# SH5_-_5V_VICOR_DCDC.net
KiCad netlist of a schematic drawn in Altium Designer
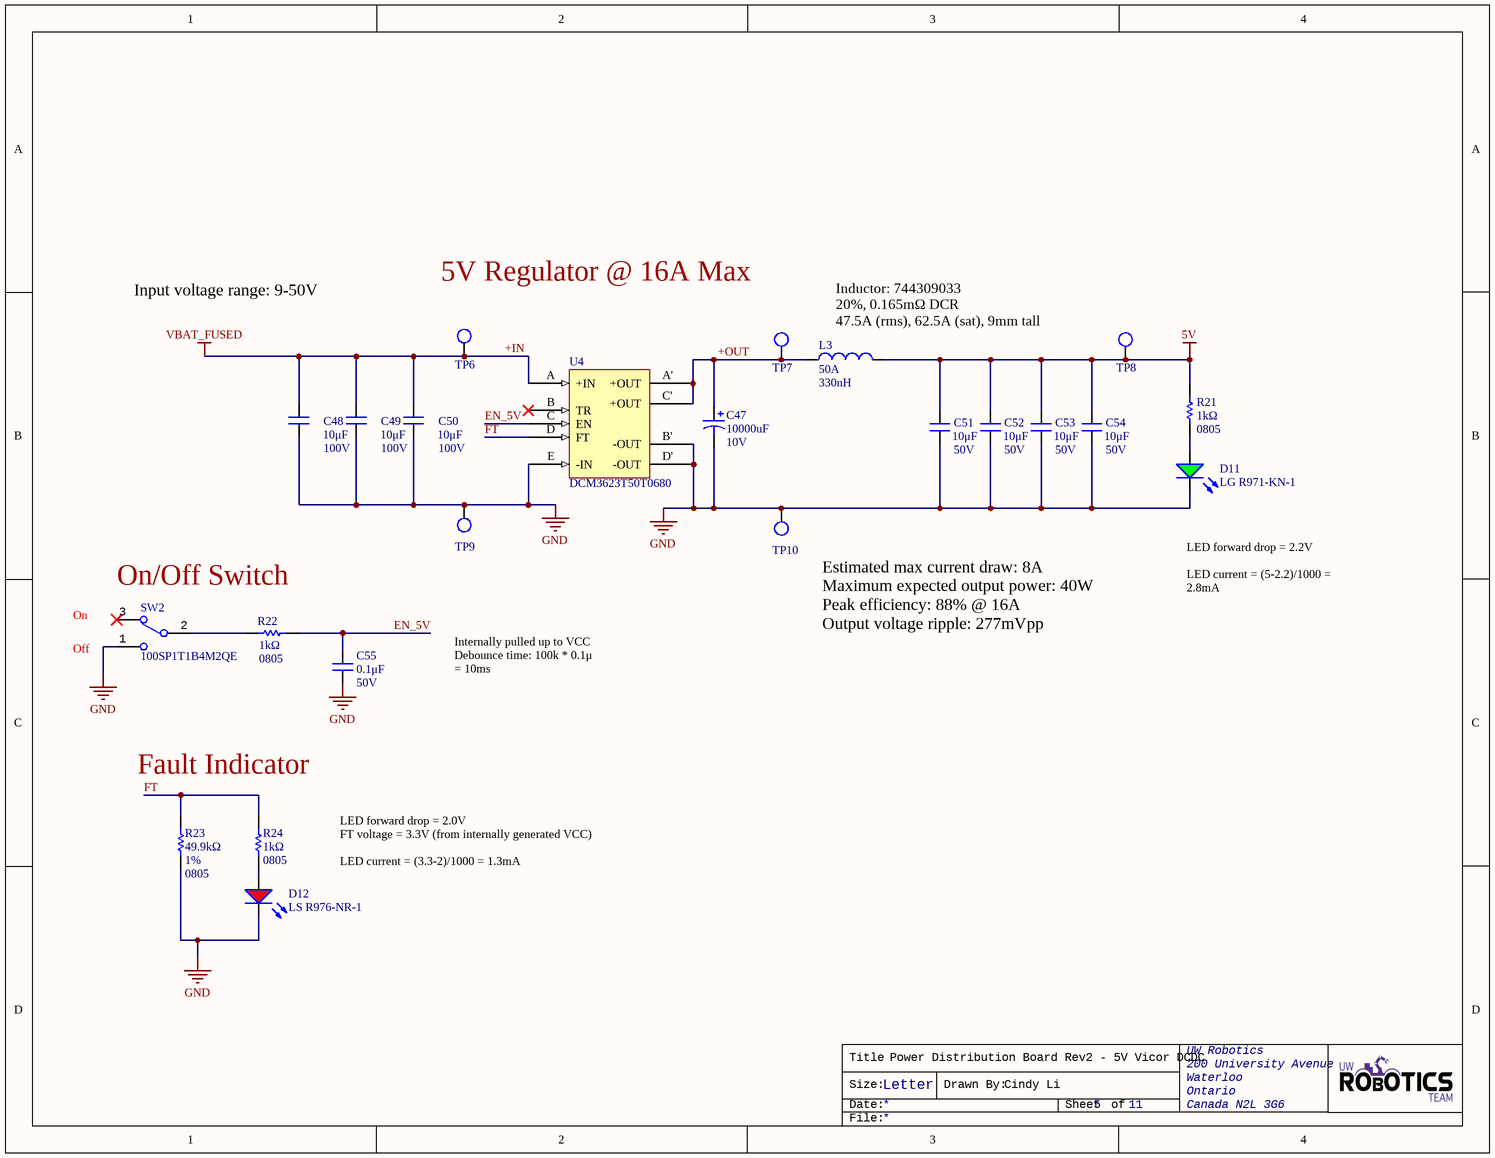
[diagram p0: SH5 - 5V VICOR DCDC.SchDoc]

(export (version "E")
  (design (tool "Eeschema 10.0.6"))
  (components
    (comp (ref "C47")
      (value "URS1A103MHD1TN")
      (footprint "CAP_UBY_18X25_NC")
      (description "CAP ALUM 10000UF 20% 10V RADIAL")
      (fields
        (field (name "TOLERANCE") "20%")
        (field (name "CAPACITANCE") "10000uF")
        (field (name "VOLTAGE RATING") "10V")
      )
      (libsource (lib "UWRT_Schematic_Library_2020") (part "URS1A103MHD1TN"))
    )
    (comp (ref "C48")
      (value "10μF")
      (footprint "CAP1210")
      (description "CAP CER 10uF 100V X7S 10% 1210")
      (fields
        (field (name "TOLERANCE") "10%")
        (field (name "VOLTAGE RATING") "100V")
        (field (name "Comment") "CAP_10uF_100V_1210")
      )
      (libsource (lib "UWRT_Schematic_Library_2020") (part "CAP_10uF_100V_1210"))
    )
    (comp (ref "C49")
      (value "10μF")
      (footprint "CAP1210")
      (description "CAP CER 10uF 100V X7S 10% 1210")
      (fields
        (field (name "TOLERANCE") "10%")
        (field (name "VOLTAGE RATING") "100V")
        (field (name "Comment") "CAP_10uF_100V_1210")
      )
      (libsource (lib "UWRT_Schematic_Library_2020") (part "CAP_10uF_100V_1210"))
    )
    (comp (ref "C50")
      (value "10μF")
      (footprint "CAP1210")
      (description "CAP CER 10uF 100V X7S 10% 1210")
      (fields
        (field (name "TOLERANCE") "10%")
        (field (name "VOLTAGE RATING") "100V")
        (field (name "Comment") "CAP_10uF_100V_1210")
      )
      (libsource (lib "UWRT_Schematic_Library_2020") (part "CAP_10uF_100V_1210"))
    )
    (comp (ref "C51")
      (value "10μF")
      (footprint "CAP1210")
      (description "CAP CER 10UF 50V X7R 1210")
      (fields
        (field (name "VOLTAGE RATING") "50V")
        (field (name "TOLERANCE") "20%")
        (field (name "Comment") "CAP_10uF_50V_1210")
      )
      (libsource (lib "UWRT_Schematic_Library_2020") (part "CAP_10uF_50V_1210"))
    )
    (comp (ref "C52")
      (value "10μF")
      (footprint "CAP1210")
      (description "CAP CER 10UF 50V X7R 1210")
      (fields
        (field (name "VOLTAGE RATING") "50V")
        (field (name "TOLERANCE") "20%")
        (field (name "Comment") "CAP_10uF_50V_1210")
      )
      (libsource (lib "UWRT_Schematic_Library_2020") (part "CAP_10uF_50V_1210"))
    )
    (comp (ref "C53")
      (value "10μF")
      (footprint "CAP1210")
      (description "CAP CER 10UF 50V X7R 1210")
      (fields
        (field (name "VOLTAGE RATING") "50V")
        (field (name "TOLERANCE") "20%")
        (field (name "Comment") "CAP_10uF_50V_1210")
      )
      (libsource (lib "UWRT_Schematic_Library_2020") (part "CAP_10uF_50V_1210"))
    )
    (comp (ref "C54")
      (value "10μF")
      (footprint "CAP1210")
      (description "CAP CER 10UF 50V X7R 1210")
      (fields
        (field (name "VOLTAGE RATING") "50V")
        (field (name "TOLERANCE") "20%")
        (field (name "Comment") "CAP_10uF_50V_1210")
      )
      (libsource (lib "UWRT_Schematic_Library_2020") (part "CAP_10uF_50V_1210"))
    )
    (comp (ref "C55")
      (value "0.1μF")
      (footprint "CAP2012")
      (description "CAP CER 0.1UF 50V X7R 0805")
      (fields (field (name "VOLTAGE RATING") "50V") (field (name "TOLERANCE") "10%"))
      (libsource (lib "UWRT_Schematic_Library_2020") (part "CAP_0.1uF_50V_0805"))
    )
    (comp (ref "D11")
      (value "LG R971-KN-1")
      (footprint "LED_0805_GREEN")
      (description "LED GREEN DIFFUSED 0805 SMD")
      (libsource (lib "UWRT_Schematic_Library_2020") (part "DIO_LED_G"))
    )
    (comp (ref "D12")
      (value "LS R976-NR-1")
      (footprint "LED_0805_RED")
      (description "LED RED DIFFUSED 0805 SMD")
      (libsource (lib "UWRT_Schematic_Library_2020") (part "DIO_LED_R"))
    )
    (comp (ref "L3")
      (value "744309033")
      (footprint "WE-HCM 1390")
      (description "IND 330NH 47.5A 0.165 MOHM")
      (fields
        (field (name "TOLERANCE") "20%")
        (field (name "MAX DC CURRENT") "50A")
        (field (name "INDUCTANCE") "330nH")
      )
      (libsource (lib "UWRT_Schematic_Library_2020") (part "744309033"))
    )
    (comp (ref "R21")
      (value "1kΩ")
      (footprint "RESC2012X60N")
      (description "RES 1K OHM 1% 1/8W 0805")
      (fields (field (name "TOLERANCE") "1%") (field (name "CASE CODE (IMPERIAL)") "0805"))
      (libsource (lib "UWRT_Schematic_Library_2020") (part "RES_1kΩ_0805_1%"))
    )
    (comp (ref "R22")
      (value "1kΩ")
      (footprint "RESC2012X60N")
      (description "RES 1K OHM 1% 1/8W 0805")
      (fields (field (name "TOLERANCE") "1%") (field (name "CASE CODE (IMPERIAL)") "0805"))
      (libsource (lib "UWRT_Schematic_Library_2020") (part "RES_1kΩ_0805_1%"))
    )
    (comp (ref "R23")
      (value "49.9kΩ")
      (footprint "RESC2012X60N")
      (description "RES 49.9K OHM 1% 1/8W 0805")
      (fields (field (name "TOLERANCE") "1%") (field (name "CASE CODE (IMPERIAL)") "0805"))
      (libsource (lib "UWRT_Schematic_Library_2020") (part "RES_49.9kΩ_0805_1%"))
    )
    (comp (ref "R24")
      (value "1kΩ")
      (footprint "RESC2012X60N")
      (description "RES 1K OHM 1% 1/8W 0805")
      (fields (field (name "TOLERANCE") "1%") (field (name "CASE CODE (IMPERIAL)") "0805"))
      (libsource (lib "UWRT_Schematic_Library_2020") (part "RES_1kΩ_0805_1%"))
    )
    (comp (ref "SW2")
      (value "100SP1T1B4M2QE")
      (footprint "100SP1T1B4M2QE")
      (description "SWITCH TOGGLE SPDT 5A 120V")
      (libsource (lib "UWRT_Schematic_Library_2020") (part "SW_SPDT"))
    )
    (comp (ref "TP6")
      (value "TESTPOINT_LOOP")
      (footprint "TESTPOINT_LOOP")
      (description "PC TEST POINT MINIATURE WHITE")
      (libsource (lib "UWRT_Schematic_Library_2020") (part "TESTPOINT_LOOP"))
    )
    (comp (ref "TP7")
      (value "TESTPOINT_LOOP")
      (footprint "TESTPOINT_LOOP")
      (description "PC TEST POINT MINIATURE WHITE")
      (libsource (lib "UWRT_Schematic_Library_2020") (part "TESTPOINT_LOOP"))
    )
    (comp (ref "TP8")
      (value "TESTPOINT_LOOP")
      (footprint "TESTPOINT_LOOP")
      (description "PC TEST POINT MINIATURE WHITE")
      (libsource (lib "UWRT_Schematic_Library_2020") (part "TESTPOINT_LOOP"))
    )
    (comp (ref "TP9")
      (value "TESTPOINT_LOOP")
      (footprint "TESTPOINT_LOOP")
      (description "PC TEST POINT MINIATURE WHITE")
      (libsource (lib "UWRT_Schematic_Library_2020") (part "TESTPOINT_LOOP"))
    )
    (comp (ref "TP10")
      (value "TESTPOINT_LOOP")
      (footprint "TESTPOINT_LOOP")
      (description "PC TEST POINT MINIATURE WHITE")
      (libsource (lib "UWRT_Schematic_Library_2020") (part "TESTPOINT_LOOP"))
    )
    (comp (ref "U4")
      (value "DCM3623T50T0680")
      (footprint "DCM3623T50T0680")
      (description "DC DC CONVERTER 5V 80W")
      (libsource (lib "UWRT_Schematic_Library_2020") (part "DCM3623T50T0680"))
    )
  )
  (nets
    (net (code "1") (name "/+OUT") (class "Default")
      (node (ref "C47") (pin "1") (pinfunction "1_1") (pintype "passive"))
      (node (ref "L3") (pin "1") (pinfunction "1_1") (pintype "passive"))
      (node (ref "TP7") (pin "1") (pintype "passive"))
      (node (ref "U4") (pin "A'") (pinfunction "+OUT_A'") (pintype "passive"))
      (node (ref "U4") (pin "C'") (pinfunction "+OUT_C'") (pintype "passive"))
    )
    (net (code "2") (name "/EN_5V") (class "Default")
      (node (ref "C55") (pin "2") (pinfunction "2_2") (pintype "passive"))
      (node (ref "R22") (pin "2") (pinfunction "2_2") (pintype "passive"))
      (node (ref "U4") (pin "C") (pinfunction "EN_C") (pintype "input"))
    )
    (net (code "3") (name "/FT") (class "Default")
      (node (ref "R23") (pin "1") (pinfunction "1_1") (pintype "passive"))
      (node (ref "R24") (pin "2") (pinfunction "2_2") (pintype "passive"))
      (node (ref "U4") (pin "D") (pinfunction "FT_D") (pintype "input"))
    )
    (net (code "4") (name "5V") (class "Default")
      (node (ref "C51") (pin "2") (pinfunction "2_2") (pintype "passive"))
      (node (ref "C52") (pin "2") (pinfunction "2_2") (pintype "passive"))
      (node (ref "C53") (pin "2") (pinfunction "2_2") (pintype "passive"))
      (node (ref "C54") (pin "2") (pinfunction "2_2") (pintype "passive"))
      (node (ref "L3") (pin "2") (pinfunction "2_2") (pintype "passive"))
      (node (ref "R21") (pin "2") (pinfunction "2_2") (pintype "passive"))
      (node (ref "TP8") (pin "1") (pintype "passive"))
    )
    (net (code "5") (name "GND") (class "Default")
      (node (ref "C47") (pin "2") (pinfunction "2_2") (pintype "passive"))
      (node (ref "C48") (pin "1") (pinfunction "1_1") (pintype "passive"))
      (node (ref "C49") (pin "1") (pinfunction "1_1") (pintype "passive"))
      (node (ref "C50") (pin "1") (pinfunction "1_1") (pintype "passive"))
      (node (ref "C51") (pin "1") (pinfunction "1_1") (pintype "passive"))
      (node (ref "C52") (pin "1") (pinfunction "1_1") (pintype "passive"))
      (node (ref "C53") (pin "1") (pinfunction "1_1") (pintype "passive"))
      (node (ref "C54") (pin "1") (pinfunction "1_1") (pintype "passive"))
      (node (ref "C55") (pin "1") (pinfunction "1_1") (pintype "passive"))
      (node (ref "D11") (pin "2") (pinfunction "K_2") (pintype "passive"))
      (node (ref "D12") (pin "2") (pinfunction "K_2") (pintype "passive"))
      (node (ref "R23") (pin "2") (pinfunction "2_2") (pintype "passive"))
      (node (ref "SW2") (pin "1") (pinfunction "1_1") (pintype "passive"))
      (node (ref "TP10") (pin "1") (pintype "passive"))
      (node (ref "TP9") (pin "1") (pintype "passive"))
      (node (ref "U4") (pin "B'") (pinfunction "-OUT_B'") (pintype "passive"))
      (node (ref "U4") (pin "D'") (pinfunction "-OUT_D'") (pintype "passive"))
      (node (ref "U4") (pin "E") (pinfunction "-IN_E") (pintype "input"))
    )
    (net (code "6") (name "Net-(D11-A)") (class "Default")
      (node (ref "D11") (pin "1") (pinfunction "A_1") (pintype "passive"))
      (node (ref "R21") (pin "1") (pinfunction "1_1") (pintype "passive"))
    )
    (net (code "7") (name "Net-(D12-A)") (class "Default")
      (node (ref "D12") (pin "1") (pinfunction "A_1") (pintype "passive"))
      (node (ref "R24") (pin "1") (pinfunction "1_1") (pintype "passive"))
    )
    (net (code "8") (name "Net-(R22-Pad1)") (class "Default")
      (node (ref "R22") (pin "1") (pinfunction "1_1") (pintype "passive"))
      (node (ref "SW2") (pin "2") (pinfunction "2_2") (pintype "passive"))
    )
    (net (code "9") (name "VBAT_FUSED") (class "Default")
      (node (ref "C48") (pin "2") (pinfunction "2_2") (pintype "passive"))
      (node (ref "C49") (pin "2") (pinfunction "2_2") (pintype "passive"))
      (node (ref "C50") (pin "2") (pinfunction "2_2") (pintype "passive"))
      (node (ref "TP6") (pin "1") (pintype "passive"))
      (node (ref "U4") (pin "A") (pinfunction "+IN_A") (pintype "input"))
    )
    (net (code "10") (name "unconnected-(SW2-Pad3)") (class "Default")
      (node (ref "SW2") (pin "3") (pinfunction "3_3") (pintype "passive+no_connect"))
    )
    (net (code "11") (name "unconnected-(U4-TR-PadB)") (class "Default")
      (node (ref "U4") (pin "B") (pinfunction "TR_B") (pintype "input+no_connect"))
    )
  )
)
